# alarmclock.net
KiCad netlist of a schematic drawn in EAGLE
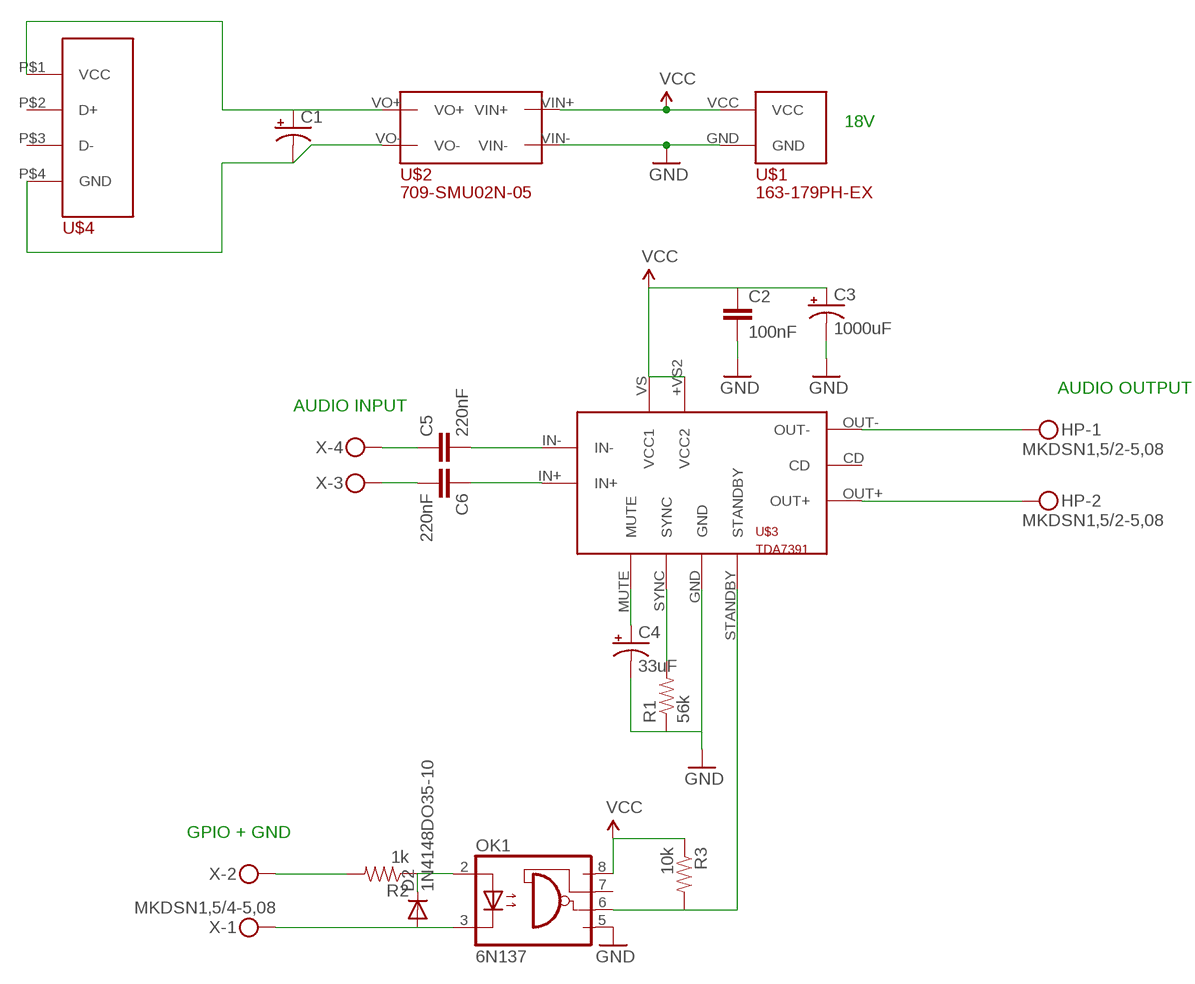
[diagram p0: schematic, sheet 1]

(export (version "E")
  (design (tool "Eeschema 10.0.6"))
  (components
    (comp (ref "C1")
      (value "CAP_POLPTH3")
      (footprint "eagle-import:CPOL-RADIAL-1000UF-63V")
      (libsource (lib "eagle-import") (part "CAP_POLPTH3"))
    )
    (comp (ref "C2")
      (value "100nF")
      (footprint "eagle-import:CAP-PTH-5MM")
      (libsource (lib "eagle-import") (part "CAPPTH1"))
    )
    (comp (ref "C3")
      (value "1000uF")
      (footprint "eagle-import:CPOL-RADIAL-1000UF-63V")
      (libsource (lib "eagle-import") (part "CAP_POLPTH3"))
    )
    (comp (ref "C4")
      (value "33uF")
      (footprint "eagle-import:CPOL-RADIAL-1000UF-25V")
      (libsource (lib "eagle-import") (part "CAP_POLPTH4"))
    )
    (comp (ref "C5")
      (value "220nF")
      (footprint "eagle-import:CAP-PTH-5MM")
      (libsource (lib "eagle-import") (part "CAPPTH1"))
    )
    (comp (ref "C6")
      (value "220nF")
      (footprint "eagle-import:CAP-PTH-5MM")
      (libsource (lib "eagle-import") (part "CAPPTH1"))
    )
    (comp (ref "D2")
      (value "1N4148DO35-10")
      (footprint "eagle-import:DO35-10")
      (libsource (lib "eagle-import") (part "1N4148DO35-10"))
    )
    (comp (ref "HP")
      (value "MKDSN1,5/2-5,08")
      (footprint "eagle-import:MKDSN1,5_2-5,08")
      (libsource (lib "eagle-import") (part "MKDSN1,5/2-5,08"))
    )
    (comp (ref "OK1")
      (value "6N137")
      (footprint "eagle-import:DIL08")
      (libsource (lib "eagle-import") (part "6N137"))
    )
    (comp (ref "R1")
      (value "56k")
      (footprint "eagle-import:AXIAL-0.5")
      (libsource (lib "eagle-import") (part "RESISTORPTH-1/2W"))
    )
    (comp (ref "R2")
      (value "1k")
      (footprint "eagle-import:AXIAL-0.5")
      (libsource (lib "eagle-import") (part "RESISTORPTH-1/2W"))
    )
    (comp (ref "R3")
      (value "10k")
      (footprint "eagle-import:AXIAL-0.5")
      (libsource (lib "eagle-import") (part "RESISTORPTH-1/2W"))
    )
    (comp (ref "U$1")
      (value "163-179PH-EX")
      (footprint "eagle-import:163-179PH-EX_DIM")
      (libsource (lib "eagle-import") (part "163-179PH-EX"))
    )
    (comp (ref "U$2")
      (value "709-SMU02N-05")
      (footprint "eagle-import:709-SMU02N-05_DIM")
      (libsource (lib "eagle-import") (part "709-SMU02N-05"))
    )
    (comp (ref "U$3")
      (value "TDA7391")
      (footprint "eagle-import:TDA7391_DIM")
      (libsource (lib "eagle-import") (part "TDA7391"))
    )
    (comp (ref "U$4")
      (value "USB_TYPEA_CONNECTOR")
      (footprint "eagle-import:USB_DIM")
      (libsource (lib "eagle-import") (part "USB_TYPEA_CONNECTOR"))
    )
    (comp (ref "X")
      (value "MKDSN1,5/4-5,08")
      (footprint "eagle-import:MKDSN1,5_4-5,08")
      (libsource (lib "eagle-import") (part "MKDSN1,5/4-5,08"))
    )
  )
  (nets
    (net (code "1") (name "GND") (class "Default")
      (node (ref "C2") (pin "2") (pinfunction "2_2") (pintype "passive"))
      (node (ref "C3") (pin "2") (pinfunction "-_2") (pintype "passive"))
      (node (ref "C4") (pin "2") (pinfunction "-_2") (pintype "passive"))
      (node (ref "OK1") (pin "5") (pinfunction "GND_5") (pintype "passive"))
      (node (ref "R1") (pin "P$1") (pinfunction "1_P$1") (pintype "passive"))
      (node (ref "U$1") (pin "GND") (pinfunction "GND_GND") (pintype "bidirectional"))
      (node (ref "U$2") (pin "VIN-") (pinfunction "VIN-_VIN-") (pintype "bidirectional"))
      (node (ref "U$3") (pin "GND") (pinfunction "GND_GND") (pintype "bidirectional"))
    )
    (net (code "2") (name "Net-(C1-+)") (class "Default")
      (node (ref "C1") (pin "1") (pinfunction "+_1") (pintype "passive"))
      (node (ref "U$2") (pin "VO+") (pinfunction "VO+_VO+") (pintype "bidirectional"))
      (node (ref "U$4") (pin "P$1") (pinfunction "VCC_P$1") (pintype "bidirectional"))
    )
    (net (code "3") (name "Net-(C1--)") (class "Default")
      (node (ref "C1") (pin "2") (pinfunction "-_2") (pintype "passive"))
      (node (ref "U$2") (pin "VO-") (pinfunction "VO-_VO-") (pintype "bidirectional"))
      (node (ref "U$4") (pin "P$4") (pinfunction "GND_P$4") (pintype "bidirectional"))
    )
    (net (code "4") (name "Net-(C4-+)") (class "Default")
      (node (ref "C4") (pin "1") (pinfunction "+_1") (pintype "passive"))
      (node (ref "U$3") (pin "MUTE") (pinfunction "MUTE_MUTE") (pintype "bidirectional"))
    )
    (net (code "5") (name "Net-(C5-Pad2)") (class "Default")
      (node (ref "C5") (pin "2") (pinfunction "2_2") (pintype "passive"))
      (node (ref "U$3") (pin "IN-") (pinfunction "IN-_IN-") (pintype "bidirectional"))
    )
    (net (code "6") (name "Net-(C6-Pad1)") (class "Default")
      (node (ref "C6") (pin "1") (pinfunction "1_1") (pintype "passive"))
      (node (ref "U$3") (pin "IN+") (pinfunction "IN+_IN+") (pintype "bidirectional"))
    )
    (net (code "7") (name "Net-(HPA-KL)") (class "Default")
      (node (ref "HP") (pin "1") (pinfunction "KL_1") (pintype "passive"))
      (node (ref "U$3") (pin "OUT-") (pinfunction "OUT-_OUT-") (pintype "bidirectional"))
    )
    (net (code "8") (name "Net-(HPB-KL)") (class "Default")
      (node (ref "HP") (pin "2") (pinfunction "KL_2") (pintype "passive"))
      (node (ref "U$3") (pin "OUT+") (pinfunction "OUT+_OUT+") (pintype "bidirectional"))
    )
    (net (code "9") (name "Net-(OK1-A)") (class "Default")
      (node (ref "D2") (pin "C") (pinfunction "C_C") (pintype "passive"))
      (node (ref "OK1") (pin "2") (pinfunction "A_2") (pintype "passive"))
      (node (ref "R2") (pin "P$1") (pinfunction "1_P$1") (pintype "passive"))
    )
    (net (code "10") (name "Net-(OK1-C)") (class "Default")
      (node (ref "D2") (pin "A") (pinfunction "A_A") (pintype "passive"))
      (node (ref "OK1") (pin "3") (pinfunction "C_3") (pintype "passive"))
      (node (ref "X") (pin "1") (pinfunction "KL_1") (pintype "passive"))
    )
    (net (code "11") (name "Net-(OK1-VO)") (class "Default")
      (node (ref "OK1") (pin "6") (pinfunction "VO_6") (pintype "passive"))
      (node (ref "R3") (pin "P$2") (pinfunction "2_P$2") (pintype "passive"))
      (node (ref "U$3") (pin "STANDBY") (pinfunction "STANDBY_STANDBY") (pintype "bidirectional"))
    )
    (net (code "12") (name "Net-(R1-2)") (class "Default")
      (node (ref "R1") (pin "P$2") (pinfunction "2_P$2") (pintype "passive"))
      (node (ref "U$3") (pin "SYNC") (pinfunction "SYNC_SYNC") (pintype "bidirectional"))
    )
    (net (code "13") (name "Net-(R2-2)") (class "Default")
      (node (ref "R2") (pin "P$2") (pinfunction "2_P$2") (pintype "passive"))
      (node (ref "X") (pin "2") (pinfunction "KL_2") (pintype "passive"))
    )
    (net (code "14") (name "Net-(XC-KL)") (class "Default")
      (node (ref "C6") (pin "2") (pinfunction "2_2") (pintype "passive"))
      (node (ref "X") (pin "3") (pinfunction "KL_3") (pintype "passive"))
    )
    (net (code "15") (name "Net-(XD-KL)") (class "Default")
      (node (ref "C5") (pin "1") (pinfunction "1_1") (pintype "passive"))
      (node (ref "X") (pin "4") (pinfunction "KL_4") (pintype "passive"))
    )
    (net (code "16") (name "VCC") (class "Default")
      (node (ref "C2") (pin "1") (pinfunction "1_1") (pintype "passive"))
      (node (ref "C3") (pin "1") (pinfunction "+_1") (pintype "passive"))
      (node (ref "OK1") (pin "8") (pinfunction "VCC_8") (pintype "passive"))
      (node (ref "R3") (pin "P$1") (pinfunction "1_P$1") (pintype "passive"))
      (node (ref "U$1") (pin "VCC") (pinfunction "VCC_VCC") (pintype "bidirectional"))
      (node (ref "U$2") (pin "VIN+") (pinfunction "VIN+_VIN+") (pintype "bidirectional"))
      (node (ref "U$3") (pin "+VS2") (pinfunction "VCC2_+VS2") (pintype "bidirectional"))
      (node (ref "U$3") (pin "VS") (pinfunction "VCC1_VS") (pintype "bidirectional"))
    )
    (net (code "17") (name "unconnected-(OK1-VE-Pad7)") (class "Default")
      (node (ref "OK1") (pin "7") (pinfunction "VE_7") (pintype "passive"))
    )
    (net (code "18") (name "unconnected-(U$3-PadCD)") (class "Default")
      (node (ref "U$3") (pin "CD") (pinfunction "CD_CD") (pintype "bidirectional"))
    )
    (net (code "19") (name "unconnected-(U$4-D+-PadP$2)") (class "Default")
      (node (ref "U$4") (pin "P$2") (pinfunction "D+_P$2") (pintype "bidirectional"))
    )
    (net (code "20") (name "unconnected-(U$4-D--PadP$3)") (class "Default")
      (node (ref "U$4") (pin "P$3") (pinfunction "D-_P$3") (pintype "bidirectional"))
    )
  )
)
